# design.net
KiCad netlist of a schematic drawn in Altium Designer
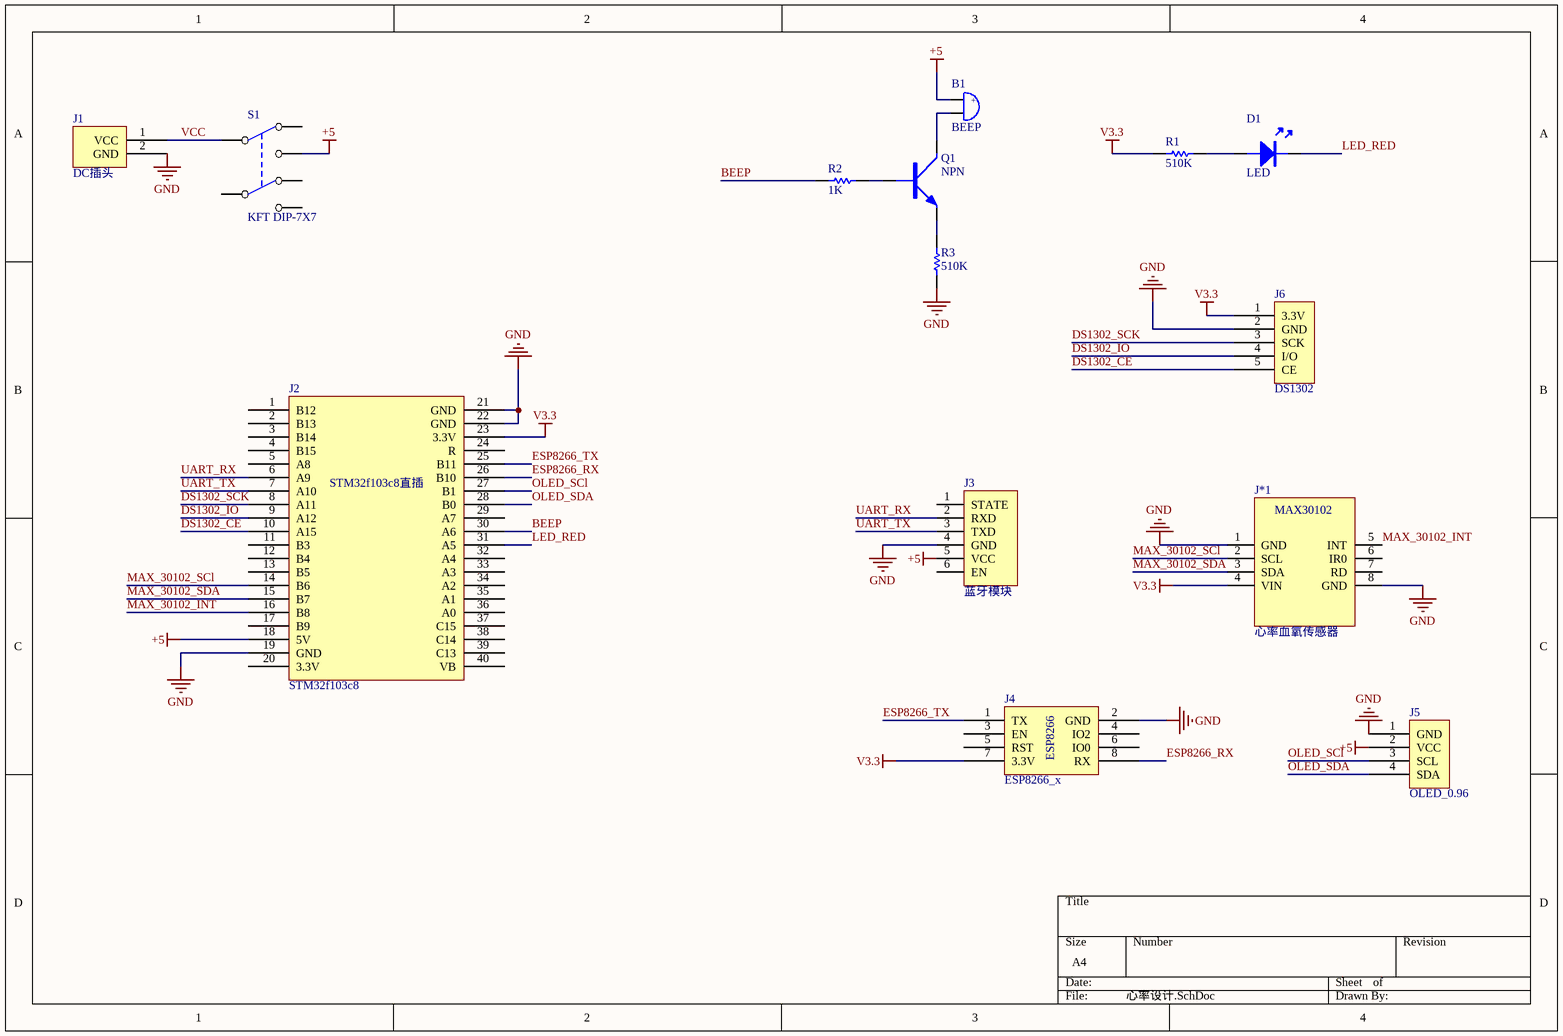
[diagram p0: 心率设计.SchDoc]

(export (version "E")
  (design (tool "Eeschema 10.0.6"))
  (components
    (comp (ref "B1")
      (value "BEEP")
      (footprint "BEEP 7.6X12X9.5")
      (description "蜂鸣器")
      (libsource (lib "蜂鸣器") (part "BEEP"))
    )
    (comp (ref "D1") (value "LED") (footprint "LED3-RED") (libsource (lib "LED") (part "LED")))
    (comp (ref "J*1")
      (value "心率血氧传感器")
      (footprint "MAX30102")
      (description "心率血氧传感器MAX30102")
      (libsource (lib "DIP_模块") (part "MAX30102"))
    )
    (comp (ref "J1") (value "DC插头") (footprint "DC插头") (libsource (lib "DIP_模块") (part "DC插头")))
    (comp (ref "J2")
      (value "STM32f103c8")
      (footprint "STM32C8t6DIP封装1")
      (description "stm32最小系统板")
      (libsource (lib "DIP_模块") (part "STM32f103c8"))
    )
    (comp (ref "J3")
      (value "蓝牙模块")
      (footprint "HC_05")
      (description "HC_05蓝牙模块")
      (libsource (lib "DIP_模块") (part "HC_05"))
    )
    (comp (ref "J4") (value "ESP8266_x") (footprint "ESP8266") (libsource (lib "DIP_模块") (part "ESP8266_1")))
    (comp (ref "J5")
      (value "OLED_0.96")
      (footprint "OLED_0.96")
      (libsource (lib "DIP_模块") (part "OLED_0.96"))
    )
    (comp (ref "J6")
      (value "DS1302")
      (footprint "Fe-HDR1X5/2.54-S")
      (libsource (lib "DIP_模块") (part "DS1302"))
    )
    (comp (ref "Q1")
      (value "NPN")
      (footprint "SOT-23")
      (description "NPN三极管")
      (libsource (lib "三极管") (part "NPN"))
    )
    (comp (ref "R1") (value "510K") (footprint "0603R") (libsource (lib "电阻") (part "RES")))
    (comp (ref "R2") (value "1K") (footprint "0603R") (libsource (lib "电阻") (part "RES")))
    (comp (ref "R3") (value "510K") (footprint "0603R") (libsource (lib "电阻") (part "RES")))
    (comp (ref "S1")
      (value "KFT DIP-7X7")
      (footprint "KFT DIP-7X7")
      (libsource (lib "电源开关") (part "KFT DIP-7X7"))
    )
  )
  (nets
    (net (code "1") (name "+5") (class "Default")
      (node (ref "B1") (pin "1") (pinfunction "1_1") (pintype "passive"))
      (node (ref "J2") (pin "18") (pinfunction "5V_18") (pintype "passive"))
      (node (ref "J3") (pin "5") (pinfunction "VCC_5") (pintype "passive"))
      (node (ref "J5") (pin "2") (pinfunction "VCC_2") (pintype "passive"))
      (node (ref "S1") (pin "1") (pinfunction "1_1") (pintype "passive"))
    )
    (net (code "2") (name "/BEEP") (class "Default")
      (node (ref "J2") (pin "30") (pinfunction "A6_30") (pintype "passive"))
      (node (ref "R2") (pin "2") (pinfunction "2_2") (pintype "passive"))
    )
    (net (code "3") (name "/DS1302_CE") (class "Default")
      (node (ref "J2") (pin "10") (pinfunction "A15_10") (pintype "passive"))
      (node (ref "J6") (pin "5") (pinfunction "CE_5") (pintype "passive"))
    )
    (net (code "4") (name "/DS1302_IO") (class "Default")
      (node (ref "J2") (pin "9") (pinfunction "A12_9") (pintype "passive"))
      (node (ref "J6") (pin "4") (pinfunction "I/O_4") (pintype "passive"))
    )
    (net (code "5") (name "/DS1302_SCK") (class "Default")
      (node (ref "J2") (pin "8") (pinfunction "A11_8") (pintype "passive"))
      (node (ref "J6") (pin "3") (pinfunction "SCK_3") (pintype "passive"))
    )
    (net (code "6") (name "/ESP8266_RX") (class "Default")
      (node (ref "J2") (pin "26") (pinfunction "B10_26") (pintype "passive"))
      (node (ref "J4") (pin "8") (pinfunction "RX_8") (pintype "passive"))
    )
    (net (code "7") (name "/ESP8266_TX") (class "Default")
      (node (ref "J2") (pin "25") (pinfunction "B11_25") (pintype "passive"))
      (node (ref "J4") (pin "1") (pinfunction "TX_1") (pintype "passive"))
    )
    (net (code "8") (name "/LED_RED") (class "Default")
      (node (ref "D1") (pin "K") (pinfunction "K_K") (pintype "passive"))
      (node (ref "J2") (pin "31") (pinfunction "A5_31") (pintype "passive"))
    )
    (net (code "9") (name "/MAX_30102_INT") (class "Default")
      (node (ref "J*1") (pin "5") (pinfunction "INT_5") (pintype "passive"))
      (node (ref "J2") (pin "16") (pinfunction "B8_16") (pintype "passive"))
    )
    (net (code "10") (name "/MAX_30102_SCl") (class "Default")
      (node (ref "J*1") (pin "2") (pinfunction "SCL_2") (pintype "passive"))
      (node (ref "J2") (pin "14") (pinfunction "B6_14") (pintype "passive"))
    )
    (net (code "11") (name "/MAX_30102_SDA") (class "Default")
      (node (ref "J*1") (pin "3") (pinfunction "SDA_3") (pintype "passive"))
      (node (ref "J2") (pin "15") (pinfunction "B7_15") (pintype "passive"))
    )
    (net (code "12") (name "/OLED_SCl") (class "Default")
      (node (ref "J2") (pin "27") (pinfunction "B1_27") (pintype "passive"))
      (node (ref "J5") (pin "3") (pinfunction "SCL_3") (pintype "passive"))
    )
    (net (code "13") (name "/OLED_SDA") (class "Default")
      (node (ref "J2") (pin "28") (pinfunction "B0_28") (pintype "passive"))
      (node (ref "J5") (pin "4") (pinfunction "SDA_4") (pintype "passive"))
    )
    (net (code "14") (name "/UART_RX") (class "Default")
      (node (ref "J2") (pin "6") (pinfunction "A9_6") (pintype "passive"))
      (node (ref "J3") (pin "2") (pinfunction "RXD_2") (pintype "passive"))
    )
    (net (code "15") (name "/UART_TX") (class "Default")
      (node (ref "J2") (pin "7") (pinfunction "A10_7") (pintype "passive"))
      (node (ref "J3") (pin "3") (pinfunction "TXD_3") (pintype "passive"))
    )
    (net (code "16") (name "/VCC") (class "Default")
      (node (ref "J1") (pin "1") (pinfunction "VCC_1") (pintype "passive"))
      (node (ref "S1") (pin "2") (pinfunction "2_2") (pintype "passive"))
    )
    (net (code "17") (name "GND") (class "Default")
      (node (ref "J*1") (pin "1") (pinfunction "GND_1") (pintype "passive"))
      (node (ref "J*1") (pin "8") (pinfunction "GND_8") (pintype "passive"))
      (node (ref "J1") (pin "2") (pinfunction "GND_2") (pintype "passive"))
      (node (ref "J2") (pin "19") (pinfunction "GND_19") (pintype "passive"))
      (node (ref "J2") (pin "21") (pinfunction "GND_21") (pintype "passive"))
      (node (ref "J2") (pin "22") (pinfunction "GND_22") (pintype "passive"))
      (node (ref "J3") (pin "4") (pinfunction "GND_4") (pintype "passive"))
      (node (ref "J4") (pin "2") (pinfunction "GND_2") (pintype "passive"))
      (node (ref "J5") (pin "1") (pinfunction "GND_1") (pintype "passive"))
      (node (ref "J6") (pin "2") (pinfunction "GND_2") (pintype "passive"))
      (node (ref "R3") (pin "1") (pinfunction "1_1") (pintype "passive"))
    )
    (net (code "18") (name "Net-(B1-Pad2)") (class "Default")
      (node (ref "B1") (pin "2") (pinfunction "2_2") (pintype "passive"))
      (node (ref "Q1") (pin "C") (pinfunction "C_C") (pintype "passive"))
    )
    (net (code "19") (name "Net-(D1-PadA)") (class "Default")
      (node (ref "D1") (pin "A") (pinfunction "A_A") (pintype "passive"))
      (node (ref "R1") (pin "2") (pinfunction "2_2") (pintype "passive"))
    )
    (net (code "20") (name "Net-(Q1-PadB)") (class "Default")
      (node (ref "Q1") (pin "B") (pinfunction "B_B") (pintype "passive"))
      (node (ref "R2") (pin "1") (pinfunction "1_1") (pintype "passive"))
    )
    (net (code "21") (name "Net-(Q1-PadE)") (class "Default")
      (node (ref "Q1") (pin "E") (pinfunction "E_E") (pintype "passive"))
      (node (ref "R3") (pin "2") (pinfunction "2_2") (pintype "passive"))
    )
    (net (code "22") (name "V3.3") (class "Default")
      (node (ref "J*1") (pin "4") (pinfunction "VIN_4") (pintype "passive"))
      (node (ref "J2") (pin "23") (pinfunction "3.3V_23") (pintype "passive"))
      (node (ref "J4") (pin "7") (pinfunction "3.3V_7") (pintype "passive"))
      (node (ref "J6") (pin "1") (pinfunction "3.3V_1") (pintype "passive"))
      (node (ref "R1") (pin "1") (pinfunction "1_1") (pintype "passive"))
    )
    (net (code "23") (name "unconnected-(J*1-IR0-Pad6)") (class "Default")
      (node (ref "J*1") (pin "6") (pinfunction "IR0_6") (pintype "passive"))
    )
    (net (code "24") (name "unconnected-(J*1-RD-Pad7)") (class "Default")
      (node (ref "J*1") (pin "7") (pinfunction "RD_7") (pintype "passive"))
    )
    (net (code "25") (name "unconnected-(J2-3.3V-Pad20)") (class "Default")
      (node (ref "J2") (pin "20") (pinfunction "3.3V_20") (pintype "passive"))
    )
    (net (code "26") (name "unconnected-(J2-A0-Pad36)") (class "Default")
      (node (ref "J2") (pin "36") (pinfunction "A0_36") (pintype "passive"))
    )
    (net (code "27") (name "unconnected-(J2-A1-Pad35)") (class "Default")
      (node (ref "J2") (pin "35") (pinfunction "A1_35") (pintype "passive"))
    )
    (net (code "28") (name "unconnected-(J2-A2-Pad34)") (class "Default")
      (node (ref "J2") (pin "34") (pinfunction "A2_34") (pintype "passive"))
    )
    (net (code "29") (name "unconnected-(J2-A3-Pad33)") (class "Default")
      (node (ref "J2") (pin "33") (pinfunction "A3_33") (pintype "passive"))
    )
    (net (code "30") (name "unconnected-(J2-A4-Pad32)") (class "Default")
      (node (ref "J2") (pin "32") (pinfunction "A4_32") (pintype "passive"))
    )
    (net (code "31") (name "unconnected-(J2-A7-Pad29)") (class "Default")
      (node (ref "J2") (pin "29") (pinfunction "A7_29") (pintype "passive"))
    )
    (net (code "32") (name "unconnected-(J2-A8-Pad5)") (class "Default")
      (node (ref "J2") (pin "5") (pinfunction "A8_5") (pintype "passive"))
    )
    (net (code "33") (name "unconnected-(J2-B3-Pad11)") (class "Default")
      (node (ref "J2") (pin "11") (pinfunction "B3_11") (pintype "passive"))
    )
    (net (code "34") (name "unconnected-(J2-B4-Pad12)") (class "Default")
      (node (ref "J2") (pin "12") (pinfunction "B4_12") (pintype "passive"))
    )
    (net (code "35") (name "unconnected-(J2-B5-Pad13)") (class "Default")
      (node (ref "J2") (pin "13") (pinfunction "B5_13") (pintype "passive"))
    )
    (net (code "36") (name "unconnected-(J2-B9-Pad17)") (class "Default")
      (node (ref "J2") (pin "17") (pinfunction "B9_17") (pintype "passive"))
    )
    (net (code "37") (name "unconnected-(J2-B12-Pad1)") (class "Default")
      (node (ref "J2") (pin "1") (pinfunction "B12_1") (pintype "passive"))
    )
    (net (code "38") (name "unconnected-(J2-B13-Pad2)") (class "Default")
      (node (ref "J2") (pin "2") (pinfunction "B13_2") (pintype "passive"))
    )
    (net (code "39") (name "unconnected-(J2-B14-Pad3)") (class "Default")
      (node (ref "J2") (pin "3") (pinfunction "B14_3") (pintype "passive"))
    )
    (net (code "40") (name "unconnected-(J2-B15-Pad4)") (class "Default")
      (node (ref "J2") (pin "4") (pinfunction "B15_4") (pintype "passive"))
    )
    (net (code "41") (name "unconnected-(J2-C13-Pad39)") (class "Default")
      (node (ref "J2") (pin "39") (pinfunction "C13_39") (pintype "passive"))
    )
    (net (code "42") (name "unconnected-(J2-C14-Pad38)") (class "Default")
      (node (ref "J2") (pin "38") (pinfunction "C14_38") (pintype "passive"))
    )
    (net (code "43") (name "unconnected-(J2-C15-Pad37)") (class "Default")
      (node (ref "J2") (pin "37") (pinfunction "C15_37") (pintype "passive"))
    )
    (net (code "44") (name "unconnected-(J2-R-Pad24)") (class "Default")
      (node (ref "J2") (pin "24") (pinfunction "R_24") (pintype "passive"))
    )
    (net (code "45") (name "unconnected-(J2-VB-Pad40)") (class "Default")
      (node (ref "J2") (pin "40") (pinfunction "VB_40") (pintype "passive"))
    )
    (net (code "46") (name "unconnected-(J3-EN-Pad6)") (class "Default")
      (node (ref "J3") (pin "6") (pinfunction "EN_6") (pintype "passive"))
    )
    (net (code "47") (name "unconnected-(J3-STATE-Pad1)") (class "Default")
      (node (ref "J3") (pin "1") (pinfunction "STATE_1") (pintype "passive"))
    )
    (net (code "48") (name "unconnected-(J4-EN-Pad3)") (class "Default")
      (node (ref "J4") (pin "3") (pinfunction "EN_3") (pintype "passive"))
    )
    (net (code "49") (name "unconnected-(J4-IO0-Pad6)") (class "Default")
      (node (ref "J4") (pin "6") (pinfunction "IO0_6") (pintype "passive"))
    )
    (net (code "50") (name "unconnected-(J4-IO2-Pad4)") (class "Default")
      (node (ref "J4") (pin "4") (pinfunction "IO2_4") (pintype "passive"))
    )
    (net (code "51") (name "unconnected-(J4-RST-Pad5)") (class "Default")
      (node (ref "J4") (pin "5") (pinfunction "RST_5") (pintype "passive"))
    )
    (net (code "52") (name "unconnected-(S1-Pad3)") (class "Default")
      (node (ref "S1") (pin "3") (pinfunction "3_3") (pintype "passive"))
    )
    (net (code "53") (name "unconnected-(S1-Pad4)") (class "Default")
      (node (ref "S1") (pin "4") (pinfunction "4_4") (pintype "passive"))
    )
    (net (code "54") (name "unconnected-(S1-Pad5)") (class "Default")
      (node (ref "S1") (pin "5") (pinfunction "5_5") (pintype "passive"))
    )
    (net (code "55") (name "unconnected-(S1-Pad6)") (class "Default")
      (node (ref "S1") (pin "6") (pinfunction "6_6") (pintype "passive"))
    )
  )
)
